# OPENMV4_BASE.net
KiCad netlist of a schematic drawn in Altium Designer
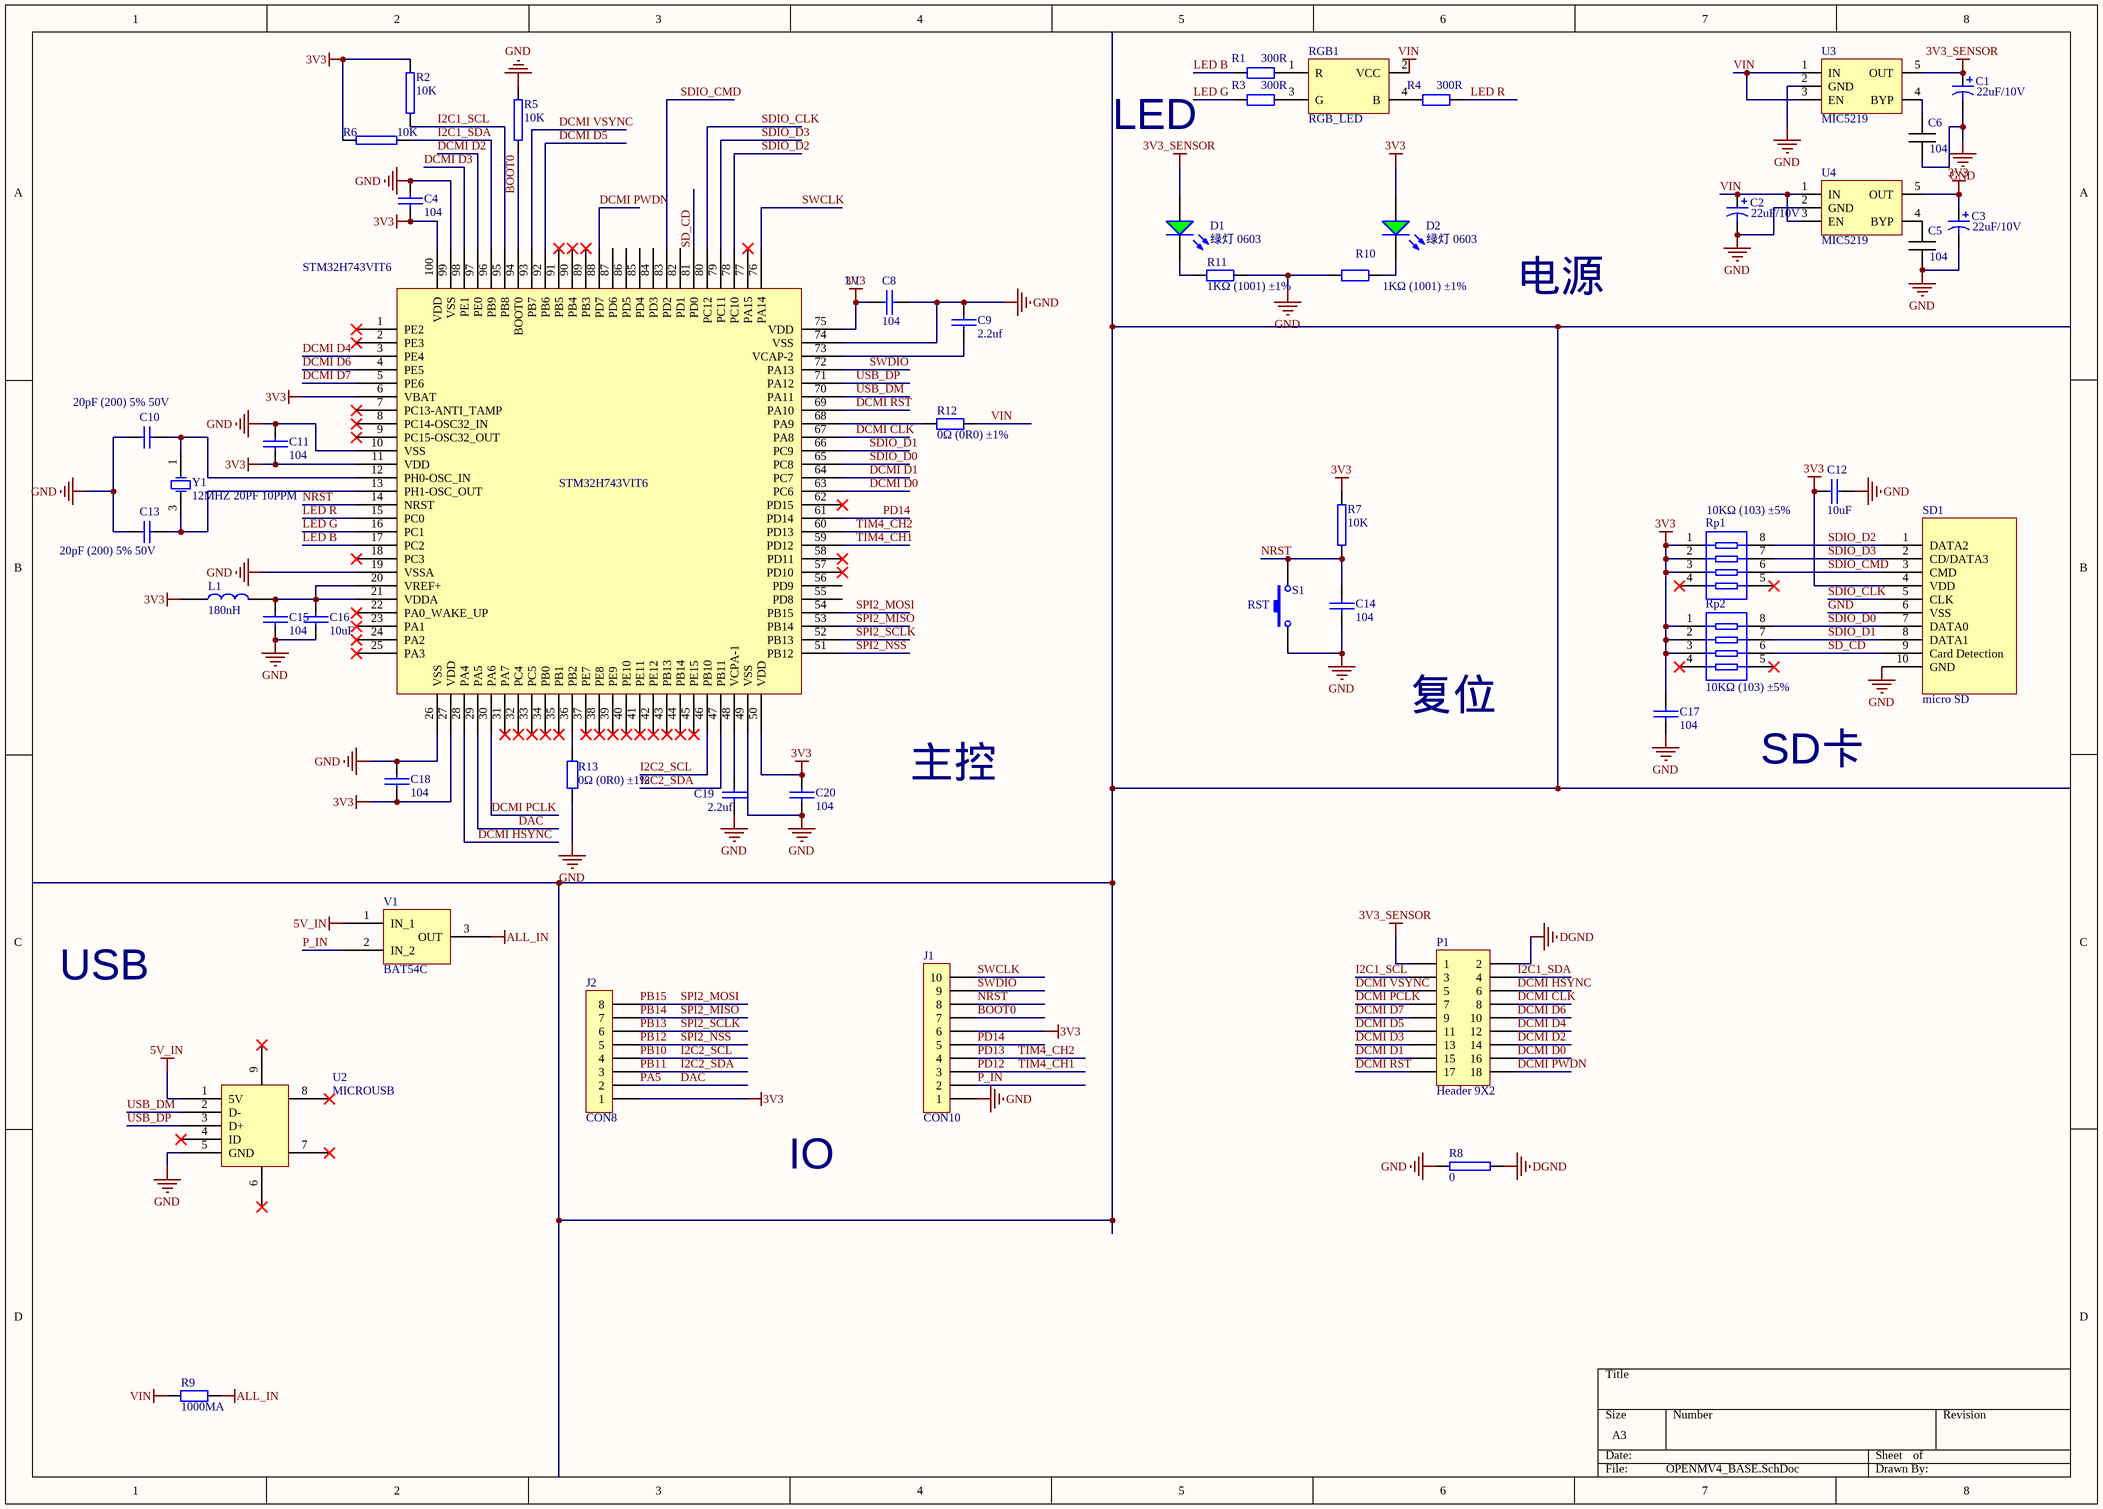
[diagram p0: OPENMV4_BASE.SchDoc]

(export (version "E")
  (design (tool "Eeschema 10.0.6"))
  (components
    (comp (ref "C1")
      (value "22uF/10V")
      (footprint "1206_C")
      (description "Polarized Capacitor (Radial)")
      (fields (field (name "Comment") "47uF") (field (name "PUBLISHER") "Altium Limited"))
      (libsource (lib "Miscellaneous Devices") (part "Cap Pol1"))
    )
    (comp (ref "C2")
      (value "22uF/10V")
      (footprint "1206_C")
      (description "Polarized Capacitor (Radial)")
      (fields (field (name "Comment") "47uF") (field (name "PUBLISHER") "Altium Limited"))
      (libsource (lib "Miscellaneous Devices") (part "Cap Pol1"))
    )
    (comp (ref "C3")
      (value "22uF/10V")
      (footprint "1206_C")
      (description "Polarized Capacitor (Radial)")
      (fields (field (name "Comment") "47uF") (field (name "PUBLISHER") "Altium Limited"))
      (libsource (lib "Miscellaneous Devices") (part "Cap Pol1"))
    )
    (comp (ref "C4") (value "104") (footprint "0603_C") (libsource (lib "自创 (1)") (part "CAP")))
    (comp (ref "C5") (value "104") (footprint "0603_C") (libsource (lib "NT-SchLibrary") (part "CAP104")))
    (comp (ref "C6") (value "104") (footprint "0603_C") (libsource (lib "NT-SchLibrary") (part "CAP104")))
    (comp (ref "C8") (value "104") (footprint "0603_C") (libsource (lib "自创 (1)") (part "CAP")))
    (comp (ref "C9") (value "2.2uf") (footprint "0603_C") (libsource (lib "自创 (1)") (part "CAP")))
    (comp (ref "C10")
      (value "20pF (200) 5% 50V")
      (footprint "0603_C")
      (description "贴片电容")
      (libsource (lib "Miscellaneous Devices LC") (part "0603 20pF (200) 5% 50V"))
    )
    (comp (ref "C11") (value "104") (footprint "0603_C") (libsource (lib "自创 (1)") (part "CAP")))
    (comp (ref "C12") (value "10uF") (footprint "0603_C") (libsource (lib "自创 (1)") (part "CAP")))
    (comp (ref "C13")
      (value "20pF (200) 5% 50V")
      (footprint "0603_C")
      (description "贴片电容")
      (libsource (lib "Miscellaneous Devices LC") (part "0603 20pF (200) 5% 50V"))
    )
    (comp (ref "C14") (value "104") (footprint "0603_C") (libsource (lib "自创 (1)") (part "CAP")))
    (comp (ref "C15") (value "104") (footprint "0603_C") (libsource (lib "自创 (1)") (part "CAP")))
    (comp (ref "C16") (value "10uF") (footprint "0603_C") (libsource (lib "自创 (1)") (part "CAP")))
    (comp (ref "C17") (value "104") (footprint "0603_C") (libsource (lib "自创 (1)") (part "CAP")))
    (comp (ref "C18") (value "104") (footprint "0603_C") (libsource (lib "自创 (1)") (part "CAP")))
    (comp (ref "C19") (value "2.2uf") (footprint "0603_C") (libsource (lib "自创 (1)") (part "CAP")))
    (comp (ref "C20") (value "104") (footprint "0603_C") (libsource (lib "自创 (1)") (part "CAP")))
    (comp (ref "D1")
      (value "绿灯 0603")
      (footprint "0603_LED_S1")
      (description "发光二极管")
      (libsource (lib "Miscellaneous Devices LC") (part "0603 绿灯"))
    )
    (comp (ref "D2")
      (value "绿灯 0603")
      (footprint "0603_LED_S1")
      (description "发光二极管")
      (libsource (lib "Miscellaneous Devices LC") (part "0603 绿灯"))
    )
    (comp (ref "J1") (value "CON10") (footprint "HDR1X10") (libsource (lib "自创") (part "CON10")))
    (comp (ref "J2") (value "CON8") (footprint "HDR1X8") (libsource (lib "自创") (part "CON8")))
    (comp (ref "L1") (value "180nH") (footprint "0603_L") (libsource (lib "自创 (1)") (part "Inductor")))
    (comp (ref "P1")
      (value "Header 9X2")
      (footprint "HDR2X9")
      (description "Header, 9-Pin, Dual row")
      (fields (field (name "PUBLISHER") "Altium Limited"))
      (libsource (lib "Miscellaneous Connectors") (part "Header 9X2"))
    )
    (comp (ref "R1")
      (value "300R")
      (footprint "0603_R")
      (description "Resistor")
      (fields (field (name "Comment") "1K") (field (name "PUBLISHER") "Altium Limited"))
      (libsource (lib "Miscellaneous Devices") (part "Res2"))
    )
    (comp (ref "R2") (value "10K") (footprint "0603_R") (libsource (lib "自创 (1)") (part "RES")))
    (comp (ref "R3")
      (value "300R")
      (footprint "0603_R")
      (description "Resistor")
      (fields (field (name "Comment") "1K") (field (name "PUBLISHER") "Altium Limited"))
      (libsource (lib "Miscellaneous Devices") (part "Res2"))
    )
    (comp (ref "R4")
      (value "300R")
      (footprint "0603_R")
      (description "Resistor")
      (fields (field (name "Comment") "1K") (field (name "PUBLISHER") "Altium Limited"))
      (libsource (lib "Miscellaneous Devices") (part "Res2"))
    )
    (comp (ref "R5") (value "10K") (footprint "0603_R") (libsource (lib "自创 (1)") (part "RES")))
    (comp (ref "R6") (value "10K") (footprint "0603_R") (libsource (lib "自创 (1)") (part "RES")))
    (comp (ref "R7") (value "10K") (footprint "0603_R") (libsource (lib "自创 (1)") (part "RES")))
    (comp (ref "R8") (value "0") (footprint "0603_R") (libsource (lib "自创 (1)") (part "RES")))
    (comp (ref "R9")
      (value "1000MA")
      (footprint "0603_R")
      (description "Resistor")
      (fields (field (name "Comment") "1A保险丝") (field (name "PUBLISHER") "Altium Limited"))
      (libsource (lib "XKZ") (part "Res2"))
    )
    (comp (ref "R10")
      (value "1KΩ (1001) ±1%")
      (footprint "0603_R")
      (description "贴片电阻")
      (libsource (lib "Miscellaneous Devices LC") (part "0603 1KΩ (1001) 1%"))
    )
    (comp (ref "R11")
      (value "1KΩ (1001) ±1%")
      (footprint "0603_R")
      (description "贴片电阻")
      (libsource (lib "Miscellaneous Devices LC") (part "0603 1KΩ (1001) 1%"))
    )
    (comp (ref "R12")
      (value "0Ω (0R0) ±1%")
      (footprint "0603_R")
      (description "贴片电阻")
      (libsource (lib "Miscellaneous Devices LC") (part "0603 0Ω (0R0) 1%"))
    )
    (comp (ref "R13")
      (value "0Ω (0R0) ±1%")
      (footprint "0603_R")
      (description "贴片电阻")
      (libsource (lib "") (part "0603 0Ω (0R0) 1%_1"))
    )
    (comp (ref "RGB1")
      (value "RGB_LED")
      (footprint "RGB3528")
      (description "三色高亮LED")
      (libsource (lib "Schlib1") (part "RGB_LED"))
    )
    (comp (ref "Rp1")
      (value "10KΩ (103) ±5%")
      (footprint "0603_Rx4")
      (description "贴片排阻")
      (libsource (lib "Miscellaneous Devices LC") (part "0603*4  10KΩ (103) 5%"))
    )
    (comp (ref "Rp2")
      (value "10KΩ (103) ±5%")
      (footprint "0603_Rx4")
      (description "贴片排阻")
      (libsource (lib "Miscellaneous Devices LC") (part "0603*4  10KΩ (103) 5%"))
    )
    (comp (ref "S1")
      (value "RST")
      (footprint "KEY")
      (description "Switch")
      (fields (field (name "PUBLISHER") "Altium Limited"))
      (libsource (lib "自创 (1)") (part "SW-PB"))
    )
    (comp (ref "SD1") (value "micro SD") (footprint "SD") (libsource (lib "XKZ") (part "micro SD")))
    (comp (ref "U1")
      (value "STM32H743VIT6")
      (footprint "LQFP-100_14x14x05P")
      (libsource (lib "XKZ") (part "STM32H743VIT6"))
    )
    (comp (ref "U2") (value "MICROUSB") (footprint "micro usb") (libsource (lib "Schlib1") (part "MICROUSB")))
    (comp (ref "U3")
      (value "MIC5219")
      (footprint "SOT-23-5")
      (description "3.3V 降压芯片")
      (libsource (lib "NT-SchLibrary") (part "MIC5219"))
    )
    (comp (ref "U4")
      (value "MIC5219")
      (footprint "SOT-23-5")
      (description "3.3V 降压芯片")
      (libsource (lib "NT-SchLibrary") (part "MIC5219"))
    )
    (comp (ref "V1") (value "BAT54C") (footprint "SOT-23(SOT-23-3)") (libsource (lib "XKZ") (part "BAT54C")))
    (comp (ref "Y1")
      (value "12MHZ 20PF 10PPM")
      (footprint "SMD-3225_4P")
      (description "贴片晶振")
      (libsource (lib "Miscellaneous Devices LC") (part "SMD-3225_4P  12MHZ 20PF 10PPM"))
    )
  )
  (nets
    (net (code "1") (name "/BOOT0") (class "Default")
      (node (ref "J1") (pin "7") (pinfunction "7_7") (pintype "passive"))
      (node (ref "R5") (pin "1") (pinfunction "1_1") (pintype "passive"))
      (node (ref "U1") (pin "94") (pinfunction "BOOT0_94") (pintype "passive"))
    )
    (net (code "2") (name "/DAC") (class "Default")
      (node (ref "J2") (pin "2") (pinfunction "2_2") (pintype "passive"))
      (node (ref "U1") (pin "29") (pinfunction "PA5_29") (pintype "passive"))
    )
    (net (code "3") (name "/DCMI CLK") (class "Default")
      (node (ref "P1") (pin "8") (pinfunction "8_8") (pintype "passive"))
      (node (ref "U1") (pin "67") (pinfunction "PA8_67") (pintype "passive"))
    )
    (net (code "4") (name "/DCMI D0") (class "Default")
      (node (ref "P1") (pin "16") (pinfunction "16_16") (pintype "passive"))
      (node (ref "U1") (pin "63") (pinfunction "PC6_63") (pintype "passive"))
    )
    (net (code "5") (name "/DCMI D1") (class "Default")
      (node (ref "P1") (pin "15") (pinfunction "15_15") (pintype "passive"))
      (node (ref "U1") (pin "64") (pinfunction "PC7_64") (pintype "passive"))
    )
    (net (code "6") (name "/DCMI D2") (class "Default")
      (node (ref "P1") (pin "14") (pinfunction "14_14") (pintype "passive"))
      (node (ref "U1") (pin "97") (pinfunction "PE0_97") (pintype "passive"))
    )
    (net (code "7") (name "/DCMI D3") (class "Default")
      (node (ref "P1") (pin "13") (pinfunction "13_13") (pintype "passive"))
      (node (ref "U1") (pin "98") (pinfunction "PE1_98") (pintype "passive"))
    )
    (net (code "8") (name "/DCMI D4") (class "Default")
      (node (ref "P1") (pin "12") (pinfunction "12_12") (pintype "passive"))
      (node (ref "U1") (pin "3") (pinfunction "PE4_3") (pintype "passive"))
    )
    (net (code "9") (name "/DCMI D5") (class "Default")
      (node (ref "P1") (pin "11") (pinfunction "11_11") (pintype "passive"))
      (node (ref "U1") (pin "92") (pinfunction "PB6_92") (pintype "passive"))
    )
    (net (code "10") (name "/DCMI D6") (class "Default")
      (node (ref "P1") (pin "10") (pinfunction "10_10") (pintype "passive"))
      (node (ref "U1") (pin "4") (pinfunction "PE5_4") (pintype "passive"))
    )
    (net (code "11") (name "/DCMI D7") (class "Default")
      (node (ref "P1") (pin "9") (pinfunction "9_9") (pintype "passive"))
      (node (ref "U1") (pin "5") (pinfunction "PE6_5") (pintype "passive"))
    )
    (net (code "12") (name "/DCMI HSYNC") (class "Default")
      (node (ref "P1") (pin "6") (pinfunction "6_6") (pintype "passive"))
      (node (ref "U1") (pin "28") (pinfunction "PA4_28") (pintype "passive"))
    )
    (net (code "13") (name "/DCMI PCLK") (class "Default")
      (node (ref "P1") (pin "7") (pinfunction "7_7") (pintype "passive"))
      (node (ref "U1") (pin "30") (pinfunction "PA6_30") (pintype "passive"))
    )
    (net (code "14") (name "/DCMI PWDN") (class "Default")
      (node (ref "P1") (pin "18") (pinfunction "18_18") (pintype "passive"))
      (node (ref "U1") (pin "88") (pinfunction "PD7_88") (pintype "passive"))
    )
    (net (code "15") (name "/DCMI RST") (class "Default")
      (node (ref "P1") (pin "17") (pinfunction "17_17") (pintype "passive"))
      (node (ref "U1") (pin "69") (pinfunction "PA10_69") (pintype "passive"))
    )
    (net (code "16") (name "/DCMI VSYNC") (class "Default")
      (node (ref "P1") (pin "5") (pinfunction "5_5") (pintype "passive"))
      (node (ref "U1") (pin "93") (pinfunction "PB7_93") (pintype "passive"))
    )
    (net (code "17") (name "/I2C1_SCL") (class "Default")
      (node (ref "P1") (pin "3") (pinfunction "3_3") (pintype "passive"))
      (node (ref "R2") (pin "1") (pinfunction "1_1") (pintype "passive"))
      (node (ref "U1") (pin "95") (pinfunction "PB8_95") (pintype "passive"))
    )
    (net (code "18") (name "/I2C1_SDA") (class "Default")
      (node (ref "P1") (pin "4") (pinfunction "4_4") (pintype "passive"))
      (node (ref "R6") (pin "2") (pinfunction "2_2") (pintype "passive"))
      (node (ref "U1") (pin "96") (pinfunction "PB9_96") (pintype "passive"))
    )
    (net (code "19") (name "/I2C2_SCL") (class "Default")
      (node (ref "J2") (pin "4") (pinfunction "4_4") (pintype "passive"))
      (node (ref "U1") (pin "46") (pinfunction "PB10_46") (pintype "passive"))
    )
    (net (code "20") (name "/I2C2_SDA") (class "Default")
      (node (ref "J2") (pin "3") (pinfunction "3_3") (pintype "passive"))
      (node (ref "U1") (pin "47") (pinfunction "PB11_47") (pintype "passive"))
    )
    (net (code "21") (name "/LED B") (class "Default")
      (node (ref "R1") (pin "1") (pinfunction "1_1") (pintype "passive"))
      (node (ref "U1") (pin "17") (pinfunction "PC2_17") (pintype "passive"))
    )
    (net (code "22") (name "/LED G") (class "Default")
      (node (ref "R3") (pin "1") (pinfunction "1_1") (pintype "passive"))
      (node (ref "U1") (pin "16") (pinfunction "PC1_16") (pintype "passive"))
    )
    (net (code "23") (name "/LED R") (class "Default")
      (node (ref "R4") (pin "2") (pinfunction "2_2") (pintype "passive"))
      (node (ref "U1") (pin "15") (pinfunction "PC0_15") (pintype "passive"))
    )
    (net (code "24") (name "/NRST") (class "Default")
      (node (ref "C14") (pin "2") (pinfunction "2_2") (pintype "passive"))
      (node (ref "J1") (pin "8") (pinfunction "8_8") (pintype "passive"))
      (node (ref "R7") (pin "2") (pinfunction "2_2") (pintype "passive"))
      (node (ref "S1") (pin "2") (pinfunction "2_2") (pintype "passive"))
      (node (ref "U1") (pin "14") (pinfunction "NRST_14") (pintype "passive"))
    )
    (net (code "25") (name "/PB12") (class "Default")
      (node (ref "J2") (pin "5") (pinfunction "5_5") (pintype "passive"))
      (node (ref "U1") (pin "51") (pinfunction "PB12_51") (pintype "passive"))
    )
    (net (code "26") (name "/PB13") (class "Default")
      (node (ref "J2") (pin "6") (pinfunction "6_6") (pintype "passive"))
      (node (ref "U1") (pin "52") (pinfunction "PB13_52") (pintype "passive"))
    )
    (net (code "27") (name "/PB14") (class "Default")
      (node (ref "J2") (pin "7") (pinfunction "7_7") (pintype "passive"))
      (node (ref "U1") (pin "53") (pinfunction "PB14_53") (pintype "passive"))
    )
    (net (code "28") (name "/PB15") (class "Default")
      (node (ref "J2") (pin "8") (pinfunction "8_8") (pintype "passive"))
      (node (ref "U1") (pin "54") (pinfunction "PB15_54") (pintype "passive"))
    )
    (net (code "29") (name "/PD12") (class "Default")
      (node (ref "J1") (pin "3") (pinfunction "3_3") (pintype "passive"))
      (node (ref "U1") (pin "59") (pinfunction "PD12_59") (pintype "passive"))
    )
    (net (code "30") (name "/PD13") (class "Default")
      (node (ref "J1") (pin "4") (pinfunction "4_4") (pintype "passive"))
      (node (ref "U1") (pin "60") (pinfunction "PD13_60") (pintype "passive"))
    )
    (net (code "31") (name "/PD14") (class "Default")
      (node (ref "J1") (pin "5") (pinfunction "5_5") (pintype "passive"))
      (node (ref "U1") (pin "61") (pinfunction "PD14_61") (pintype "passive"))
    )
    (net (code "32") (name "/P_IN") (class "Default")
      (node (ref "J1") (pin "2") (pinfunction "2_2") (pintype "passive"))
      (node (ref "V1") (pin "2") (pinfunction "IN_2_2") (pintype "passive"))
    )
    (net (code "33") (name "/SDIO_CLK") (class "Default")
      (node (ref "SD1") (pin "5") (pinfunction "CLK_5") (pintype "passive"))
      (node (ref "U1") (pin "80") (pinfunction "PC12_80") (pintype "passive"))
    )
    (net (code "34") (name "/SDIO_CMD") (class "Default")
      (node (ref "Rp1") (pin "6") (pinfunction "6_6") (pintype "passive"))
      (node (ref "SD1") (pin "3") (pinfunction "CMD_3") (pintype "passive"))
      (node (ref "U1") (pin "83") (pinfunction "PD2_83") (pintype "passive"))
    )
    (net (code "35") (name "/SDIO_D0") (class "Default")
      (node (ref "Rp2") (pin "8") (pinfunction "8_8") (pintype "passive"))
      (node (ref "SD1") (pin "7") (pinfunction "DATA0_7") (pintype "passive"))
      (node (ref "U1") (pin "65") (pinfunction "PC8_65") (pintype "passive"))
    )
    (net (code "36") (name "/SDIO_D1") (class "Default")
      (node (ref "Rp2") (pin "7") (pinfunction "7_7") (pintype "passive"))
      (node (ref "SD1") (pin "8") (pinfunction "DATA1_8") (pintype "passive"))
      (node (ref "U1") (pin "66") (pinfunction "PC9_66") (pintype "passive"))
    )
    (net (code "37") (name "/SDIO_D2") (class "Default")
      (node (ref "Rp1") (pin "8") (pinfunction "8_8") (pintype "passive"))
      (node (ref "SD1") (pin "1") (pinfunction "DATA2_1") (pintype "passive"))
      (node (ref "U1") (pin "78") (pinfunction "PC10_78") (pintype "passive"))
    )
    (net (code "38") (name "/SDIO_D3") (class "Default")
      (node (ref "Rp1") (pin "7") (pinfunction "7_7") (pintype "passive"))
      (node (ref "SD1") (pin "2") (pinfunction "CD/DATA3_2") (pintype "passive"))
      (node (ref "U1") (pin "79") (pinfunction "PC11_79") (pintype "passive"))
    )
    (net (code "39") (name "/SD_CD") (class "Default")
      (node (ref "Rp2") (pin "6") (pinfunction "6_6") (pintype "passive"))
      (node (ref "SD1") (pin "9") (pinfunction "Card_Detection_9") (pintype "passive"))
      (node (ref "U1") (pin "81") (pinfunction "PD0_81") (pintype "passive"))
    )
    (net (code "40") (name "/SWCLK") (class "Default")
      (node (ref "J1") (pin "10") (pinfunction "10_10") (pintype "passive"))
      (node (ref "U1") (pin "76") (pinfunction "PA14_76") (pintype "passive"))
    )
    (net (code "41") (name "/SWDIO") (class "Default")
      (node (ref "J1") (pin "9") (pinfunction "9_9") (pintype "passive"))
      (node (ref "U1") (pin "72") (pinfunction "PA13_72") (pintype "passive"))
    )
    (net (code "42") (name "/USB_DM") (class "Default")
      (node (ref "U1") (pin "70") (pinfunction "PA11_70") (pintype "passive"))
      (node (ref "U2") (pin "2") (pinfunction "D-_2") (pintype "passive"))
    )
    (net (code "43") (name "/USB_DP") (class "Default")
      (node (ref "U1") (pin "71") (pinfunction "PA12_71") (pintype "passive"))
      (node (ref "U2") (pin "3") (pinfunction "D+_3") (pintype "passive"))
    )
    (net (code "44") (name "3V3") (class "Default")
      (node (ref "C11") (pin "2") (pinfunction "2_2") (pintype "passive"))
      (node (ref "C12") (pin "2") (pinfunction "2_2") (pintype "passive"))
      (node (ref "C17") (pin "2") (pinfunction "2_2") (pintype "passive"))
      (node (ref "C18") (pin "2") (pinfunction "2_2") (pintype "passive"))
      (node (ref "C20") (pin "2") (pinfunction "2_2") (pintype "passive"))
      (node (ref "C3") (pin "1") (pinfunction "1_1") (pintype "passive"))
      (node (ref "C4") (pin "2") (pinfunction "2_2") (pintype "passive"))
      (node (ref "C8") (pin "2") (pinfunction "2_2") (pintype "passive"))
      (node (ref "D2") (pin "A") (pinfunction "A_A") (pintype "passive"))
      (node (ref "J1") (pin "6") (pinfunction "6_6") (pintype "passive"))
      (node (ref "J2") (pin "1") (pinfunction "1_1") (pintype "passive"))
      (node (ref "L1") (pin "1") (pinfunction "1_1") (pintype "passive"))
      (node (ref "R2") (pin "2") (pinfunction "2_2") (pintype "passive"))
      (node (ref "R6") (pin "1") (pinfunction "1_1") (pintype "passive"))
      (node (ref "R7") (pin "1") (pinfunction "1_1") (pintype "passive"))
      (node (ref "Rp1") (pin "1") (pinfunction "1_1") (pintype "passive"))
      (node (ref "Rp1") (pin "2") (pinfunction "2_2") (pintype "passive"))
      (node (ref "Rp1") (pin "3") (pinfunction "3_3") (pintype "passive"))
      (node (ref "Rp2") (pin "1") (pinfunction "1_1") (pintype "passive"))
      (node (ref "Rp2") (pin "2") (pinfunction "2_2") (pintype "passive"))
      (node (ref "Rp2") (pin "3") (pinfunction "3_3") (pintype "passive"))
      (node (ref "SD1") (pin "4") (pinfunction "VDD_4") (pintype "passive"))
      (node (ref "U1") (pin "100") (pinfunction "VDD_100") (pintype "passive"))
      (node (ref "U1") (pin "11") (pinfunction "VDD_11") (pintype "passive"))
      (node (ref "U1") (pin "27") (pinfunction "VDD_27") (pintype "passive"))
      (node (ref "U1") (pin "50") (pinfunction "VDD_50") (pintype "passive"))
      (node (ref "U1") (pin "6") (pinfunction "VBAT_6") (pintype "passive"))
      (node (ref "U1") (pin "75") (pinfunction "VDD_75") (pintype "passive"))
      (node (ref "U4") (pin "5") (pinfunction "OUT_5") (pintype "passive"))
    )
    (net (code "45") (name "3V3_SENSOR") (class "Default")
      (node (ref "C1") (pin "1") (pinfunction "1_1") (pintype "passive"))
      (node (ref "D1") (pin "A") (pinfunction "A_A") (pintype "passive"))
      (node (ref "P1") (pin "1") (pinfunction "1_1") (pintype "passive"))
      (node (ref "U3") (pin "5") (pinfunction "OUT_5") (pintype "passive"))
    )
    (net (code "46") (name "5V_IN") (class "Default")
      (node (ref "U2") (pin "1") (pinfunction "5V_1") (pintype "passive"))
      (node (ref "V1") (pin "1") (pinfunction "IN_1_1") (pintype "passive"))
    )
    (net (code "47") (name "ALL_IN") (class "Default")
      (node (ref "R9") (pin "2") (pinfunction "2_2") (pintype "passive"))
      (node (ref "V1") (pin "3") (pinfunction "OUT_3") (pintype "passive"))
    )
    (net (code "48") (name "DGND") (class "Default")
      (node (ref "P1") (pin "2") (pinfunction "2_2") (pintype "passive"))
      (node (ref "R8") (pin "2") (pinfunction "2_2") (pintype "passive"))
    )
    (net (code "49") (name "GND") (class "Default")
      (node (ref "C1") (pin "2") (pinfunction "2_2") (pintype "passive"))
      (node (ref "C10") (pin "2") (pinfunction "2_2") (pintype "passive"))
      (node (ref "C11") (pin "1") (pinfunction "1_1") (pintype "passive"))
      (node (ref "C12") (pin "1") (pinfunction "1_1") (pintype "passive"))
      (node (ref "C13") (pin "2") (pinfunction "2_2") (pintype "passive"))
      (node (ref "C14") (pin "1") (pinfunction "1_1") (pintype "passive"))
      (node (ref "C15") (pin "2") (pinfunction "2_2") (pintype "passive"))
      (node (ref "C16") (pin "2") (pinfunction "2_2") (pintype "passive"))
      (node (ref "C17") (pin "1") (pinfunction "1_1") (pintype "passive"))
      (node (ref "C18") (pin "1") (pinfunction "1_1") (pintype "passive"))
      (node (ref "C19") (pin "2") (pinfunction "2_2") (pintype "passive"))
      (node (ref "C2") (pin "2") (pinfunction "2_2") (pintype "passive"))
      (node (ref "C20") (pin "1") (pinfunction "1_1") (pintype "passive"))
      (node (ref "C3") (pin "2") (pinfunction "2_2") (pintype "passive"))
      (node (ref "C4") (pin "1") (pinfunction "1_1") (pintype "passive"))
      (node (ref "C5") (pin "1") (pinfunction "1_1") (pintype "passive"))
      (node (ref "C6") (pin "1") (pinfunction "1_1") (pintype "passive"))
      (node (ref "C8") (pin "1") (pinfunction "1_1") (pintype "passive"))
      (node (ref "C9") (pin "2") (pinfunction "2_2") (pintype "passive"))
      (node (ref "J1") (pin "1") (pinfunction "1_1") (pintype "passive"))
      (node (ref "R10") (pin "1") (pinfunction "1_1") (pintype "passive"))
      (node (ref "R11") (pin "2") (pinfunction "2_2") (pintype "passive"))
      (node (ref "R13") (pin "2") (pinfunction "2_2") (pintype "passive"))
      (node (ref "R5") (pin "2") (pinfunction "2_2") (pintype "passive"))
      (node (ref "R8") (pin "1") (pinfunction "1_1") (pintype "passive"))
      (node (ref "S1") (pin "1") (pinfunction "1_1") (pintype "passive"))
      (node (ref "SD1") (pin "10") (pinfunction "GND_10") (pintype "passive"))
      (node (ref "SD1") (pin "6") (pinfunction "VSS_6") (pintype "passive"))
      (node (ref "U1") (pin "10") (pinfunction "VSS_10") (pintype "passive"))
      (node (ref "U1") (pin "19") (pinfunction "VSSA_19") (pintype "passive"))
      (node (ref "U1") (pin "26") (pinfunction "VSS_26") (pintype "passive"))
      (node (ref "U1") (pin "49") (pinfunction "VSS_49") (pintype "passive"))
      (node (ref "U1") (pin "74") (pinfunction "VSS_74") (pintype "passive"))
      (node (ref "U1") (pin "99") (pinfunction "VSS_99") (pintype "passive"))
      (node (ref "U2") (pin "5") (pinfunction "GND_5") (pintype "passive"))
      (node (ref "U3") (pin "2") (pinfunction "GND_2") (pintype "passive"))
      (node (ref "U4") (pin "2") (pinfunction "GND_2") (pintype "passive"))
    )
    (net (code "50") (name "Net-(D1-PadK)") (class "Default")
      (node (ref "D1") (pin "K") (pinfunction "K_K") (pintype "passive"))
      (node (ref "R11") (pin "1") (pinfunction "1_1") (pintype "passive"))
    )
    (net (code "51") (name "Net-(D2-PadK)") (class "Default")
      (node (ref "D2") (pin "K") (pinfunction "K_K") (pintype "passive"))
      (node (ref "R10") (pin "2") (pinfunction "2_2") (pintype "passive"))
    )
    (net (code "52") (name "Net-(RGB1-B)") (class "Default")
      (node (ref "R4") (pin "1") (pinfunction "1_1") (pintype "passive"))
      (node (ref "RGB1") (pin "4") (pinfunction "B_4") (pintype "passive"))
    )
    (net (code "53") (name "Net-(RGB1-G)") (class "Default")
      (node (ref "R3") (pin "2") (pinfunction "2_2") (pintype "passive"))
      (node (ref "RGB1") (pin "3") (pinfunction "G_3") (pintype "passive"))
    )
    (net (code "54") (name "Net-(RGB1-R)") (class "Default")
      (node (ref "R1") (pin "2") (pinfunction "2_2") (pintype "passive"))
      (node (ref "RGB1") (pin "1") (pinfunction "R_1") (pintype "passive"))
    )
    (net (code "55") (name "Net-(U1-PA9)") (class "Default")
      (node (ref "R12") (pin "1") (pinfunction "1_1") (pintype "passive"))
      (node (ref "U1") (pin "68") (pinfunction "PA9_68") (pintype "passive"))
    )
    (net (code "56") (name "Net-(U1-PB2)") (class "Default")
      (node (ref "R13") (pin "1") (pinfunction "1_1") (pintype "passive"))
      (node (ref "U1") (pin "36") (pinfunction "PB2_36") (pintype "passive"))
    )
    (net (code "57") (name "Net-(U1-PH0-OSC_IN)") (class "Default")
      (node (ref "C10") (pin "1") (pinfunction "1_1") (pintype "passive"))
      (node (ref "U1") (pin "12") (pinfunction "PH0-OSC_IN_12") (pintype "passive"))
      (node (ref "Y1") (pin "1") (pinfunction "OSC1_1") (pintype "passive"))
    )
    (net (code "58") (name "Net-(U1-PH1-OSC_OUT)") (class "Default")
      (node (ref "C13") (pin "1") (pinfunction "1_1") (pintype "passive"))
      (node (ref "U1") (pin "13") (pinfunction "PH1-OSC_OUT_13") (pintype "passive"))
      (node (ref "Y1") (pin "3") (pinfunction "OSC2_3") (pintype "passive"))
    )
    (net (code "59") (name "Net-(U1-VCAP-2)") (class "Default")
      (node (ref "C9") (pin "1") (pinfunction "1_1") (pintype "passive"))
      (node (ref "U1") (pin "73") (pinfunction "VCAP-2_73") (pintype "passive"))
    )
    (net (code "60") (name "Net-(U1-VCPA-1)") (class "Default")
      (node (ref "C19") (pin "1") (pinfunction "1_1") (pintype "passive"))
      (node (ref "U1") (pin "48") (pinfunction "VCPA-1_48") (pintype "passive"))
    )
    (net (code "61") (name "Net-(U1-VDDA)") (class "Default")
      (node (ref "C15") (pin "1") (pinfunction "1_1") (pintype "passive"))
      (node (ref "C16") (pin "1") (pinfunction "1_1") (pintype "passive"))
      (node (ref "L1") (pin "2") (pinfunction "2_2") (pintype "passive"))
      (node (ref "U1") (pin "20") (pinfunction "VREF+_20") (pintype "passive"))
      (node (ref "U1") (pin "21") (pinfunction "VDDA_21") (pintype "passive"))
    )
    (net (code "62") (name "Net-(U3-BYP)") (class "Default")
      (node (ref "C6") (pin "2") (pinfunction "2_2") (pintype "passive"))
      (node (ref "U3") (pin "4") (pinfunction "BYP_4") (pintype "passive"))
    )
    (net (code "63") (name "Net-(U4-BYP)") (class "Default")
      (node (ref "C5") (pin "2") (pinfunction "2_2") (pintype "passive"))
      (node (ref "U4") (pin "4") (pinfunction "BYP_4") (pintype "passive"))
    )
    (net (code "64") (name "VIN") (class "Default")
      (node (ref "C2") (pin "1") (pinfunction "1_1") (pintype "passive"))
      (node (ref "R12") (pin "2") (pinfunction "2_2") (pintype "passive"))
      (node (ref "R9") (pin "1") (pinfunction "1_1") (pintype "passive"))
      (node (ref "RGB1") (pin "2") (pinfunction "VCC_2") (pintype "passive"))
      (node (ref "U3") (pin "1") (pinfunction "IN_1") (pintype "passive"))
      (node (ref "U3") (pin "3") (pinfunction "EN_3") (pintype "passive"))
      (node (ref "U4") (pin "1") (pinfunction "IN_1") (pintype "passive"))
      (node (ref "U4") (pin "3") (pinfunction "EN_3") (pintype "passive"))
    )
    (net (code "65") (name "unconnected-(Rp1-Pad4)") (class "Default")
      (node (ref "Rp1") (pin "4") (pinfunction "4_4") (pintype "passive+no_connect"))
    )
    (net (code "66") (name "unconnected-(Rp1-Pad5)") (class "Default")
      (node (ref "Rp1") (pin "5") (pinfunction "5_5") (pintype "passive+no_connect"))
    )
    (net (code "67") (name "unconnected-(Rp2-Pad4)") (class "Default")
      (node (ref "Rp2") (pin "4") (pinfunction "4_4") (pintype "passive+no_connect"))
    )
    (net (code "68") (name "unconnected-(Rp2-Pad5)") (class "Default")
      (node (ref "Rp2") (pin "5") (pinfunction "5_5") (pintype "passive+no_connect"))
    )
    (net (code "69") (name "unconnected-(U1-PA0_WAKE_UP-Pad22)") (class "Default")
      (node (ref "U1") (pin "22") (pinfunction "PA0_WAKE_UP_22") (pintype "passive+no_connect"))
    )
    (net (code "70") (name "unconnected-(U1-PA1-Pad23)") (class "Default")
      (node (ref "U1") (pin "23") (pinfunction "PA1_23") (pintype "passive+no_connect"))
    )
    (net (code "71") (name "unconnected-(U1-PA2-Pad24)") (class "Default")
      (node (ref "U1") (pin "24") (pinfunction "PA2_24") (pintype "passive+no_connect"))
    )
    (net (code "72") (name "unconnected-(U1-PA3-Pad25)") (class "Default")
      (node (ref "U1") (pin "25") (pinfunction "PA3_25") (pintype "passive+no_connect"))
    )
    (net (code "73") (name "unconnected-(U1-PA7-Pad31)") (class "Default")
      (node (ref "U1") (pin "31") (pinfunction "PA7_31") (pintype "passive+no_connect"))
    )
    (net (code "74") (name "unconnected-(U1-PA15-Pad77)") (class "Default")
      (node (ref "U1") (pin "77") (pinfunction "PA15_77") (pintype "passive+no_connect"))
    )
    (net (code "75") (name "unconnected-(U1-PB0-Pad34)") (class "Default")
      (node (ref "U1") (pin "34") (pinfunction "PB0_34") (pintype "passive+no_connect"))
    )
    (net (code "76") (name "unconnected-(U1-PB1-Pad35)") (class "Default")
      (node (ref "U1") (pin "35") (pinfunction "PB1_35") (pintype "passive+no_connect"))
    )
    (net (code "77") (name "unconnected-(U1-PB3-Pad89)") (class "Default")
      (node (ref "U1") (pin "89") (pinfunction "PB3_89") (pintype "passive+no_connect"))
    )
    (net (code "78") (name "unconnected-(U1-PB4-Pad90)") (class "Default")
      (node (ref "U1") (pin "90") (pinfunction "PB4_90") (pintype "passive+no_connect"))
    )
    (net (code "79") (name "unconnected-(U1-PB5-Pad91)") (class "Default")
      (node (ref "U1") (pin "91") (pinfunction "PB5_91") (pintype "passive+no_connect"))
    )
    (net (code "80") (name "unconnected-(U1-PB13-Pad43)") (class "Default")
      (node (ref "U1") (pin "43") (pinfunction "PB13_43") (pintype "passive+no_connect"))
    )
    (net (code "81") (name "unconnected-(U1-PB14-Pad44)") (class "Default")
      (node (ref "U1") (pin "44") (pinfunction "PB14_44") (pintype "passive+no_connect"))
    )
    (net (code "82") (name "unconnected-(U1-PC3-Pad18)") (class "Default")
      (node (ref "U1") (pin "18") (pinfunction "PC3_18") (pintype "passive+no_connect"))
    )
    (net (code "83") (name "unconnected-(U1-PC4-Pad32)") (class "Default")
      (node (ref "U1") (pin "32") (pinfunction "PC4_32") (pintype "passive+no_connect"))
    )
    (net (code "84") (name "unconnected-(U1-PC5-Pad33)") (class "Default")
      (node (ref "U1") (pin "33") (pinfunction "PC5_33") (pintype "passive+no_connect"))
    )
    (net (code "85") (name "unconnected-(U1-PC13-ANTI_TAMP-Pad7)") (class "Default")
      (node (ref "U1") (pin "7") (pinfunction "PC13-ANTI_TAMP_7") (pintype "passive+no_connect"))
    )
    (net (code "86") (name "unconnected-(U1-PC14-OSC32_IN-Pad8)") (class "Default")
      (node (ref "U1") (pin "8") (pinfunction "PC14-OSC32_IN_8") (pintype "passive+no_connect"))
    )
    (net (code "87") (name "unconnected-(U1-PC15-OSC32_OUT-Pad9)") (class "Default")
      (node (ref "U1") (pin "9") (pinfunction "PC15-OSC32_OUT_9") (pintype "passive+no_connect"))
    )
    (net (code "88") (name "unconnected-(U1-PD1-Pad82)") (class "Default")
      (node (ref "U1") (pin "82") (pinfunction "PD1_82") (pintype "passive"))
    )
    (net (code "89") (name "unconnected-(U1-PD3-Pad84)") (class "Default")
      (node (ref "U1") (pin "84") (pinfunction "PD3_84") (pintype "passive"))
    )
    (net (code "90") (name "unconnected-(U1-PD4-Pad85)") (class "Default")
      (node (ref "U1") (pin "85") (pinfunction "PD4_85") (pintype "passive"))
    )
    (net (code "91") (name "unconnected-(U1-PD5-Pad86)") (class "Default")
      (node (ref "U1") (pin "86") (pinfunction "PD5_86") (pintype "passive"))
    )
    (net (code "92") (name "unconnected-(U1-PD6-Pad87)") (class "Default")
      (node (ref "U1") (pin "87") (pinfunction "PD6_87") (pintype "passive"))
    )
    (net (code "93") (name "unconnected-(U1-PD8-Pad55)") (class "Default")
      (node (ref "U1") (pin "55") (pinfunction "PD8_55") (pintype "passive"))
    )
    (net (code "94") (name "unconnected-(U1-PD9-Pad56)") (class "Default")
      (node (ref "U1") (pin "56") (pinfunction "PD9_56") (pintype "passive"))
    )
    (net (code "95") (name "unconnected-(U1-PD10-Pad57)") (class "Default")
      (node (ref "U1") (pin "57") (pinfunction "PD10_57") (pintype "passive+no_connect"))
    )
    (net (code "96") (name "unconnected-(U1-PD11-Pad58)") (class "Default")
      (node (ref "U1") (pin "58") (pinfunction "PD11_58") (pintype "passive+no_connect"))
    )
    (net (code "97") (name "unconnected-(U1-PD15-Pad62)") (class "Default")
      (node (ref "U1") (pin "62") (pinfunction "PD15_62") (pintype "passive+no_connect"))
    )
    (net (code "98") (name "unconnected-(U1-PE2-Pad1)") (class "Default")
      (node (ref "U1") (pin "1") (pinfunction "PE2_1") (pintype "passive+no_connect"))
    )
    (net (code "99") (name "unconnected-(U1-PE3-Pad2)") (class "Default")
      (node (ref "U1") (pin "2") (pinfunction "PE3_2") (pintype "passive+no_connect"))
    )
    (net (code "100") (name "unconnected-(U1-PE7-Pad37)") (class "Default")
      (node (ref "U1") (pin "37") (pinfunction "PE7_37") (pintype "passive+no_connect"))
    )
    (net (code "101") (name "unconnected-(U1-PE8-Pad38)") (class "Default")
      (node (ref "U1") (pin "38") (pinfunction "PE8_38") (pintype "passive+no_connect"))
    )
    (net (code "102") (name "unconnected-(U1-PE9-Pad39)") (class "Default")
      (node (ref "U1") (pin "39") (pinfunction "PE9_39") (pintype "passive+no_connect"))
    )
    (net (code "103") (name "unconnected-(U1-PE10-Pad40)") (class "Default")
      (node (ref "U1") (pin "40") (pinfunction "PE10_40") (pintype "passive+no_connect"))
    )
    (net (code "104") (name "unconnected-(U1-PE11-Pad41)") (class "Default")
      (node (ref "U1") (pin "41") (pinfunction "PE11_41") (pintype "passive+no_connect"))
    )
    (net (code "105") (name "unconnected-(U1-PE12-Pad42)") (class "Default")
      (node (ref "U1") (pin "42") (pinfunction "PE12_42") (pintype "passive+no_connect"))
    )
    (net (code "106") (name "unconnected-(U1-PE15-Pad45)") (class "Default")
      (node (ref "U1") (pin "45") (pinfunction "PE15_45") (pintype "passive+no_connect"))
    )
    (net (code "107") (name "unconnected-(U2-ID-Pad4)") (class "Default")
      (node (ref "U2") (pin "4") (pinfunction "ID_4") (pintype "passive+no_connect"))
    )
    (net (code "108") (name "unconnected-(U2-Pad6)") (class "Default")
      (node (ref "U2") (pin "6") (pinfunction "6_6") (pintype "passive+no_connect"))
    )
    (net (code "109") (name "unconnected-(U2-Pad7)") (class "Default")
      (node (ref "U2") (pin "7") (pinfunction "7_7") (pintype "passive+no_connect"))
    )
    (net (code "110") (name "unconnected-(U2-Pad8)") (class "Default")
      (node (ref "U2") (pin "8") (pinfunction "8_8") (pintype "passive+no_connect"))
    )
    (net (code "111") (name "unconnected-(U2-Pad9)") (class "Default")
      (node (ref "U2") (pin "9") (pinfunction "9_9") (pintype "passive+no_connect"))
    )
  )
)
